# adapter-50-100mil-x10.net
KiCad netlist of a schematic drawn in Altium Designer
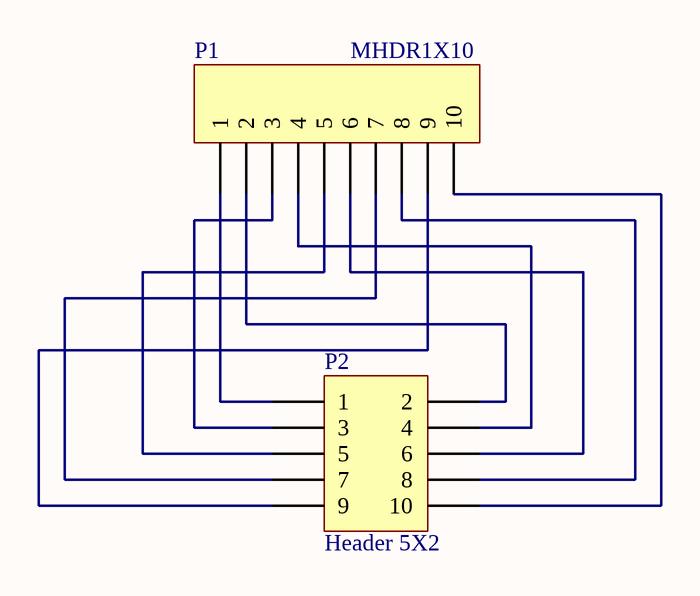
[diagram p0: adapter-50-100mil-x10.SchDoc]

(export (version "E")
  (design (tool "Eeschema 10.0.6"))
  (components
    (comp (ref "P1")
      (value "MHDR1X10")
      (footprint "MHDR1X10")
      (description "Header, 10-Pin")
      (fields (field (name "PUBLISHER") "Altium Limited"))
      (libsource (lib "Miscellaneous Connectors") (part "MHDR1X10"))
    )
    (comp (ref "P2")
      (value "Header 5X2")
      (footprint "HDR2X5")
      (description "Header, 5-Pin, Dual row")
      (fields (field (name "PUBLISHER") "Altium Limited"))
      (libsource (lib "Miscellaneous Connectors") (part "Header 5X2"))
    )
  )
  (nets
    (net (code "1") (name "Net-(P1-Pad1)") (class "Default")
      (node (ref "P1") (pin "1") (pinfunction "1_1") (pintype "passive"))
      (node (ref "P2") (pin "1") (pinfunction "1_1") (pintype "passive"))
    )
    (net (code "2") (name "Net-(P1-Pad2)") (class "Default")
      (node (ref "P1") (pin "2") (pinfunction "2_2") (pintype "passive"))
      (node (ref "P2") (pin "2") (pinfunction "2_2") (pintype "passive"))
    )
    (net (code "3") (name "Net-(P1-Pad3)") (class "Default")
      (node (ref "P1") (pin "3") (pinfunction "3_3") (pintype "passive"))
      (node (ref "P2") (pin "3") (pinfunction "3_3") (pintype "passive"))
    )
    (net (code "4") (name "Net-(P1-Pad4)") (class "Default")
      (node (ref "P1") (pin "4") (pinfunction "4_4") (pintype "passive"))
      (node (ref "P2") (pin "4") (pinfunction "4_4") (pintype "passive"))
    )
    (net (code "5") (name "Net-(P1-Pad5)") (class "Default")
      (node (ref "P1") (pin "5") (pinfunction "5_5") (pintype "passive"))
      (node (ref "P2") (pin "5") (pinfunction "5_5") (pintype "passive"))
    )
    (net (code "6") (name "Net-(P1-Pad6)") (class "Default")
      (node (ref "P1") (pin "6") (pinfunction "6_6") (pintype "passive"))
      (node (ref "P2") (pin "6") (pinfunction "6_6") (pintype "passive"))
    )
    (net (code "7") (name "Net-(P1-Pad7)") (class "Default")
      (node (ref "P1") (pin "7") (pinfunction "7_7") (pintype "passive"))
      (node (ref "P2") (pin "7") (pinfunction "7_7") (pintype "passive"))
    )
    (net (code "8") (name "Net-(P1-Pad8)") (class "Default")
      (node (ref "P1") (pin "8") (pinfunction "8_8") (pintype "passive"))
      (node (ref "P2") (pin "8") (pinfunction "8_8") (pintype "passive"))
    )
    (net (code "9") (name "Net-(P1-Pad9)") (class "Default")
      (node (ref "P1") (pin "9") (pinfunction "9_9") (pintype "passive"))
      (node (ref "P2") (pin "9") (pinfunction "9_9") (pintype "passive"))
    )
    (net (code "10") (name "Net-(P1-Pad10)") (class "Default")
      (node (ref "P1") (pin "10") (pinfunction "10_10") (pintype "passive"))
      (node (ref "P2") (pin "10") (pinfunction "10_10") (pintype "passive"))
    )
  )
)
